# power_supply_diagram.net
KiCad netlist of a schematic drawn in EAGLE
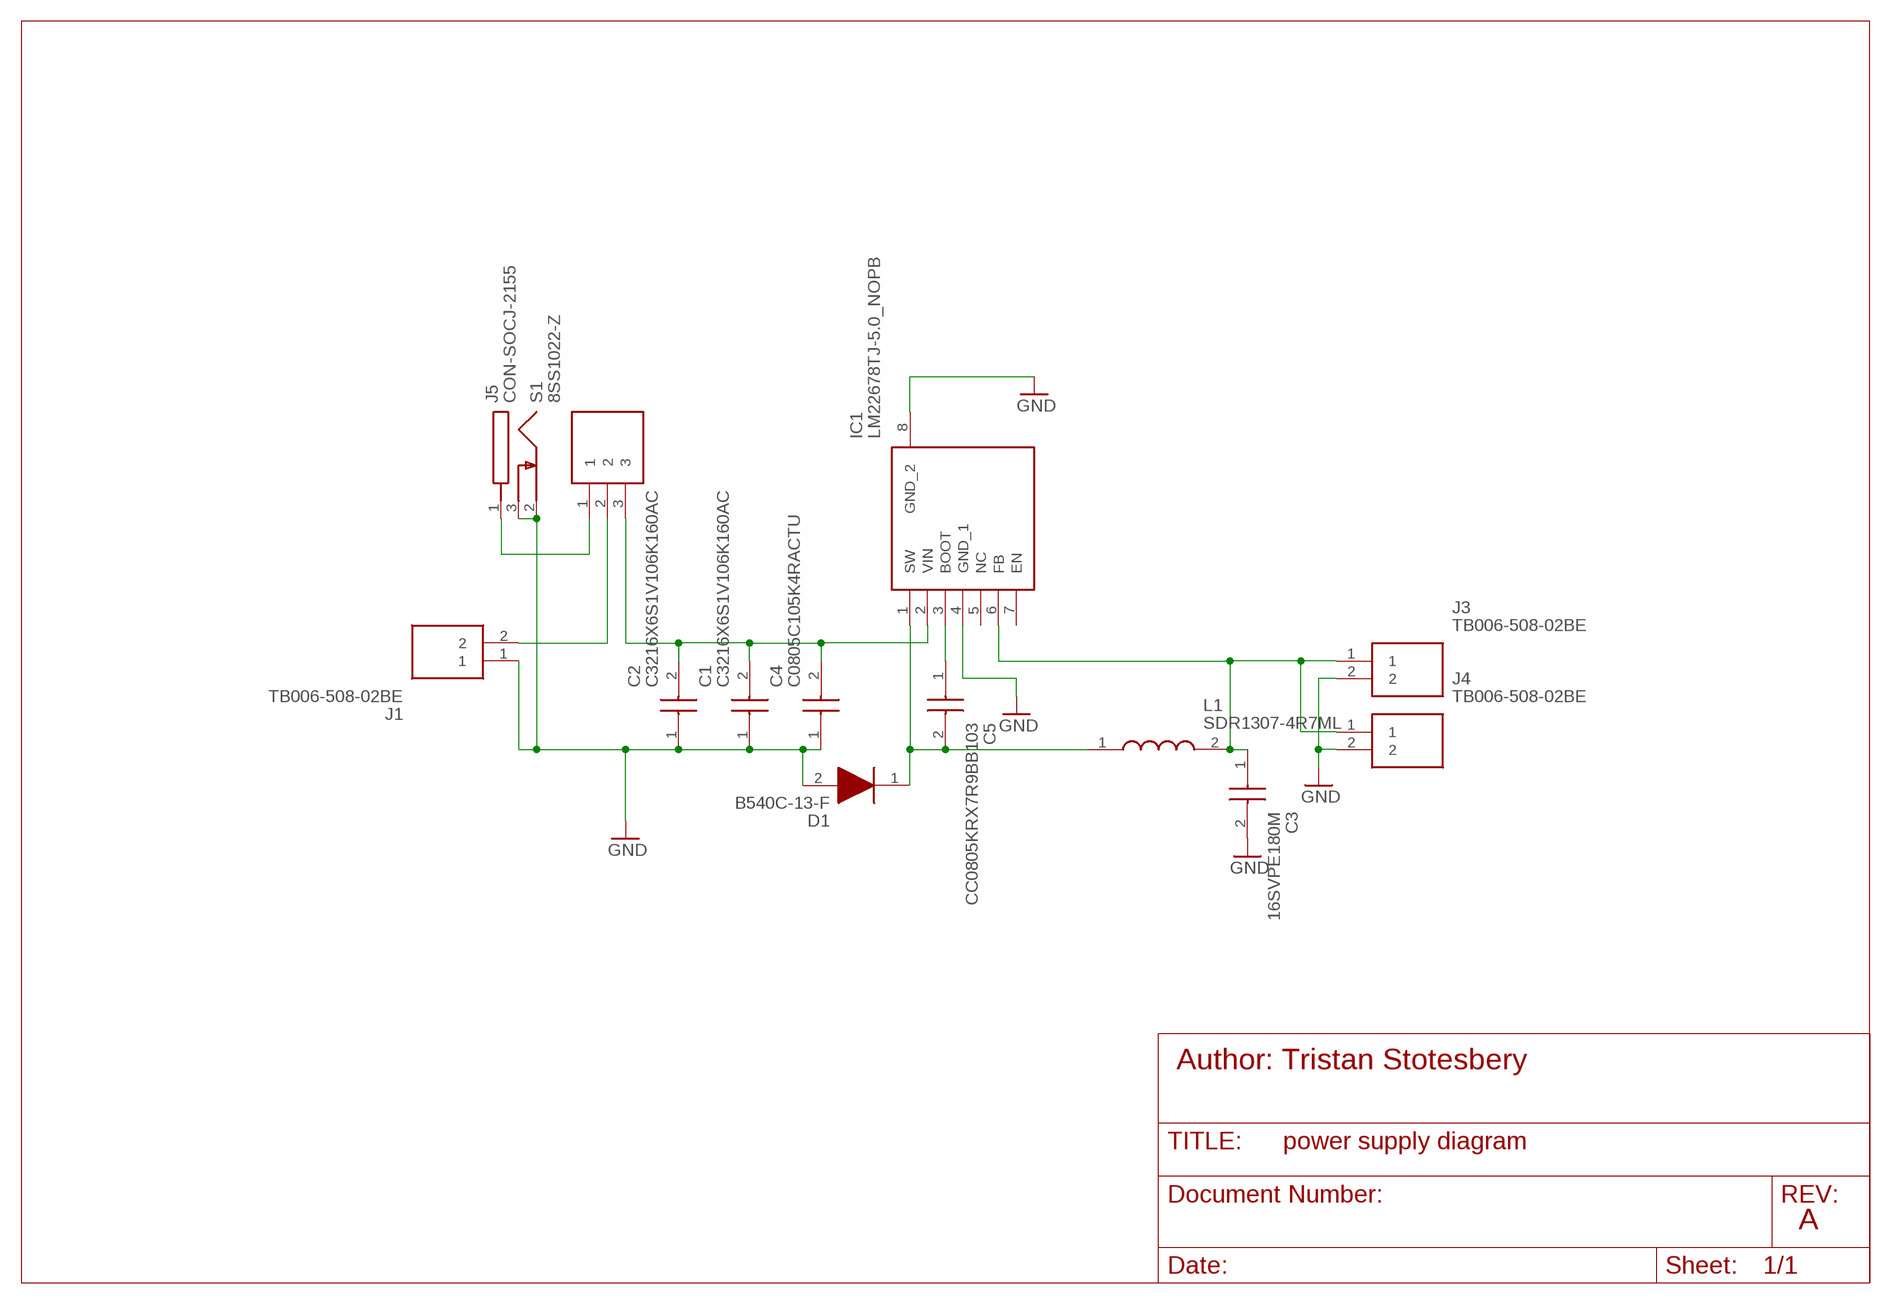
[diagram p0: schematic, sheet 1]

(export (version "E")
  (design (tool "Eeschema 10.0.6"))
  (components
    (comp (ref "C1")
      (value "C3216X6S1V106K160AC")
      (footprint "eagle-import:CAPC3216X180N")
      (fields (field (name "MOUSER_PART_NUMBER") "810-C3216X6S1V106K6A"))
      (libsource (lib "eagle-import") (part "C3216X6S1V106K160AC"))
    )
    (comp (ref "C2")
      (value "C3216X6S1V106K160AC")
      (footprint "eagle-import:CAPC3216X180N")
      (fields (field (name "MOUSER_PART_NUMBER") "810-C3216X6S1V106K6A"))
      (libsource (lib "eagle-import") (part "C3216X6S1V106K160AC"))
    )
    (comp (ref "C3")
      (value "16SVPE180M")
      (footprint "eagle-import:16SVPE180M")
      (fields (field (name "MOUSER_PART_NUMBER") "667-16SVPE180M"))
      (libsource (lib "eagle-import") (part "16SVPE180M"))
    )
    (comp (ref "C4")
      (value "C0805C105K4RACTU")
      (footprint "eagle-import:CAPC2012X100N")
      (fields (field (name "MOUSER_PART_NUMBER") "80-C0805C105K4R"))
      (libsource (lib "eagle-import") (part "C0805C105K4RACTU"))
    )
    (comp (ref "C5")
      (value "CC0805KRX7R9BB103")
      (footprint "eagle-import:CAPC2012X135N")
      (fields (field (name "MOUSER_PART_NUMBER") "603-CC805KRX7R9BB103"))
      (libsource (lib "eagle-import") (part "CC0805KRX7R9BB103"))
    )
    (comp (ref "D1")
      (value "B540C-13-F")
      (footprint "eagle-import:DIOM7959X250N")
      (fields (field (name "MOUSER_PART_NUMBER") "621-B540C-F"))
      (libsource (lib "eagle-import") (part "B540C-13-F"))
    )
    (comp (ref "IC1")
      (value "LM22678TJ-5.0_NOPB")
      (footprint "eagle-import:LM22678TJ50NOPB")
      (fields
        (field (name "MANUFACTURER_PART_NUMBER") "LM22678TJ-5.0/NOPB")
        (field (name "MOUSER_PART_NUMBER") "926-LM22678TJ50NOPB")
      )
      (libsource (lib "eagle-import") (part "LM22678TJ-5.0_NOPB"))
    )
    (comp (ref "J1")
      (value "TB006-508-02BE")
      (footprint "eagle-import:TB00650802BE")
      (fields (field (name "MOUSER_PART_NUMBER") "490-TB006-508-02BE"))
      (libsource (lib "eagle-import") (part "TB006-508-02BE"))
    )
    (comp (ref "J3")
      (value "TB006-508-02BE")
      (footprint "eagle-import:TB00650802BE")
      (fields (field (name "MOUSER_PART_NUMBER") "490-TB006-508-02BE"))
      (libsource (lib "eagle-import") (part "TB006-508-02BE"))
    )
    (comp (ref "J4")
      (value "TB006-508-02BE")
      (footprint "eagle-import:TB00650802BE")
      (fields (field (name "MOUSER_PART_NUMBER") "490-TB006-508-02BE"))
      (libsource (lib "eagle-import") (part "TB006-508-02BE"))
    )
    (comp (ref "J5")
      (value "CON-SOCJ-2155")
      (footprint "eagle-import:CONSOCJ2155")
      (fields (field (name "MOUSER_PART_NUMBER") "992-CON-SOCJ-2155"))
      (libsource (lib "eagle-import") (part "CON-SOCJ-2155"))
    )
    (comp (ref "L1")
      (value "SDR1307-4R7ML")
      (footprint "eagle-import:SDR1307-220ML")
      (fields (field (name "MOUSER_PART_NUMBER") "652-SDR1307-4R7ML"))
      (libsource (lib "eagle-import") (part "SDR1307-4R7ML"))
    )
    (comp (ref "S1")
      (value "8SS1022-Z")
      (footprint "eagle-import:8SS1022Z")
      (fields (field (name "MOUSER_PART_NUMBER") "229-8SS1022-Z"))
      (libsource (lib "eagle-import") (part "8SS1022-Z"))
    )
  )
  (nets
    (net (code "1") (name "GND") (class "Default")
      (node (ref "C1") (pin "1") (pinfunction "1_1") (pintype "bidirectional"))
      (node (ref "C2") (pin "1") (pinfunction "1_1") (pintype "bidirectional"))
      (node (ref "C3") (pin "2") (pinfunction "2_2") (pintype "bidirectional"))
      (node (ref "C4") (pin "1") (pinfunction "1_1") (pintype "bidirectional"))
      (node (ref "D1") (pin "2") (pinfunction "A_2") (pintype "bidirectional"))
      (node (ref "IC1") (pin "4") (pinfunction "GND_1_4") (pintype "bidirectional"))
      (node (ref "IC1") (pin "8") (pinfunction "GND_2_8") (pintype "bidirectional"))
      (node (ref "J1") (pin "1") (pinfunction "1_1") (pintype "bidirectional"))
      (node (ref "J3") (pin "2") (pinfunction "2_2") (pintype "bidirectional"))
      (node (ref "J4") (pin "2") (pinfunction "2_2") (pintype "bidirectional"))
      (node (ref "J5") (pin "2") (pinfunction "2_2") (pintype "bidirectional"))
      (node (ref "J5") (pin "3") (pinfunction "3_3") (pintype "bidirectional"))
    )
    (net (code "2") (name "Net-(D1-K)") (class "Default")
      (node (ref "C5") (pin "2") (pinfunction "2_2") (pintype "bidirectional"))
      (node (ref "D1") (pin "1") (pinfunction "K_1") (pintype "bidirectional"))
      (node (ref "IC1") (pin "1") (pinfunction "SW_1") (pintype "bidirectional"))
      (node (ref "L1") (pin "1") (pinfunction "1_1") (pintype "bidirectional"))
    )
    (net (code "3") (name "Net-(IC1-BOOT)") (class "Default")
      (node (ref "C5") (pin "1") (pinfunction "1_1") (pintype "bidirectional"))
      (node (ref "IC1") (pin "3") (pinfunction "BOOT_3") (pintype "bidirectional"))
    )
    (net (code "4") (name "Net-(IC1-FB)") (class "Default")
      (node (ref "C3") (pin "1") (pinfunction "1_1") (pintype "bidirectional"))
      (node (ref "IC1") (pin "6") (pinfunction "FB_6") (pintype "bidirectional"))
      (node (ref "J3") (pin "1") (pinfunction "1_1") (pintype "bidirectional"))
      (node (ref "J4") (pin "1") (pinfunction "1_1") (pintype "bidirectional"))
      (node (ref "L1") (pin "2") (pinfunction "2_2") (pintype "bidirectional"))
    )
    (net (code "5") (name "Net-(IC1-VIN)") (class "Default")
      (node (ref "C1") (pin "2") (pinfunction "2_2") (pintype "bidirectional"))
      (node (ref "C2") (pin "2") (pinfunction "2_2") (pintype "bidirectional"))
      (node (ref "C4") (pin "2") (pinfunction "2_2") (pintype "bidirectional"))
      (node (ref "IC1") (pin "2") (pinfunction "VIN_2") (pintype "bidirectional"))
      (node (ref "S1") (pin "3") (pinfunction "3_3") (pintype "bidirectional"))
    )
    (net (code "6") (name "Net-(J1-Pad2)") (class "Default")
      (node (ref "J1") (pin "2") (pinfunction "2_2") (pintype "bidirectional"))
      (node (ref "S1") (pin "2") (pinfunction "2_2") (pintype "bidirectional"))
    )
    (net (code "7") (name "Net-(J5-Pad1)") (class "Default")
      (node (ref "J5") (pin "1") (pinfunction "1_1") (pintype "bidirectional"))
      (node (ref "S1") (pin "1") (pinfunction "1_1") (pintype "bidirectional"))
    )
    (net (code "8") (name "unconnected-(IC1-EN-Pad7)") (class "Default")
      (node (ref "IC1") (pin "7") (pinfunction "EN_7") (pintype "bidirectional"))
    )
    (net (code "9") (name "unconnected-(IC1-NC-Pad5)") (class "Default")
      (node (ref "IC1") (pin "5") (pinfunction "NC_5") (pintype "no_connect"))
    )
  )
)
